# PSPS_AVNC_SRD_central-2020-09-19.net
KiCad netlist of a schematic drawn in EAGLE
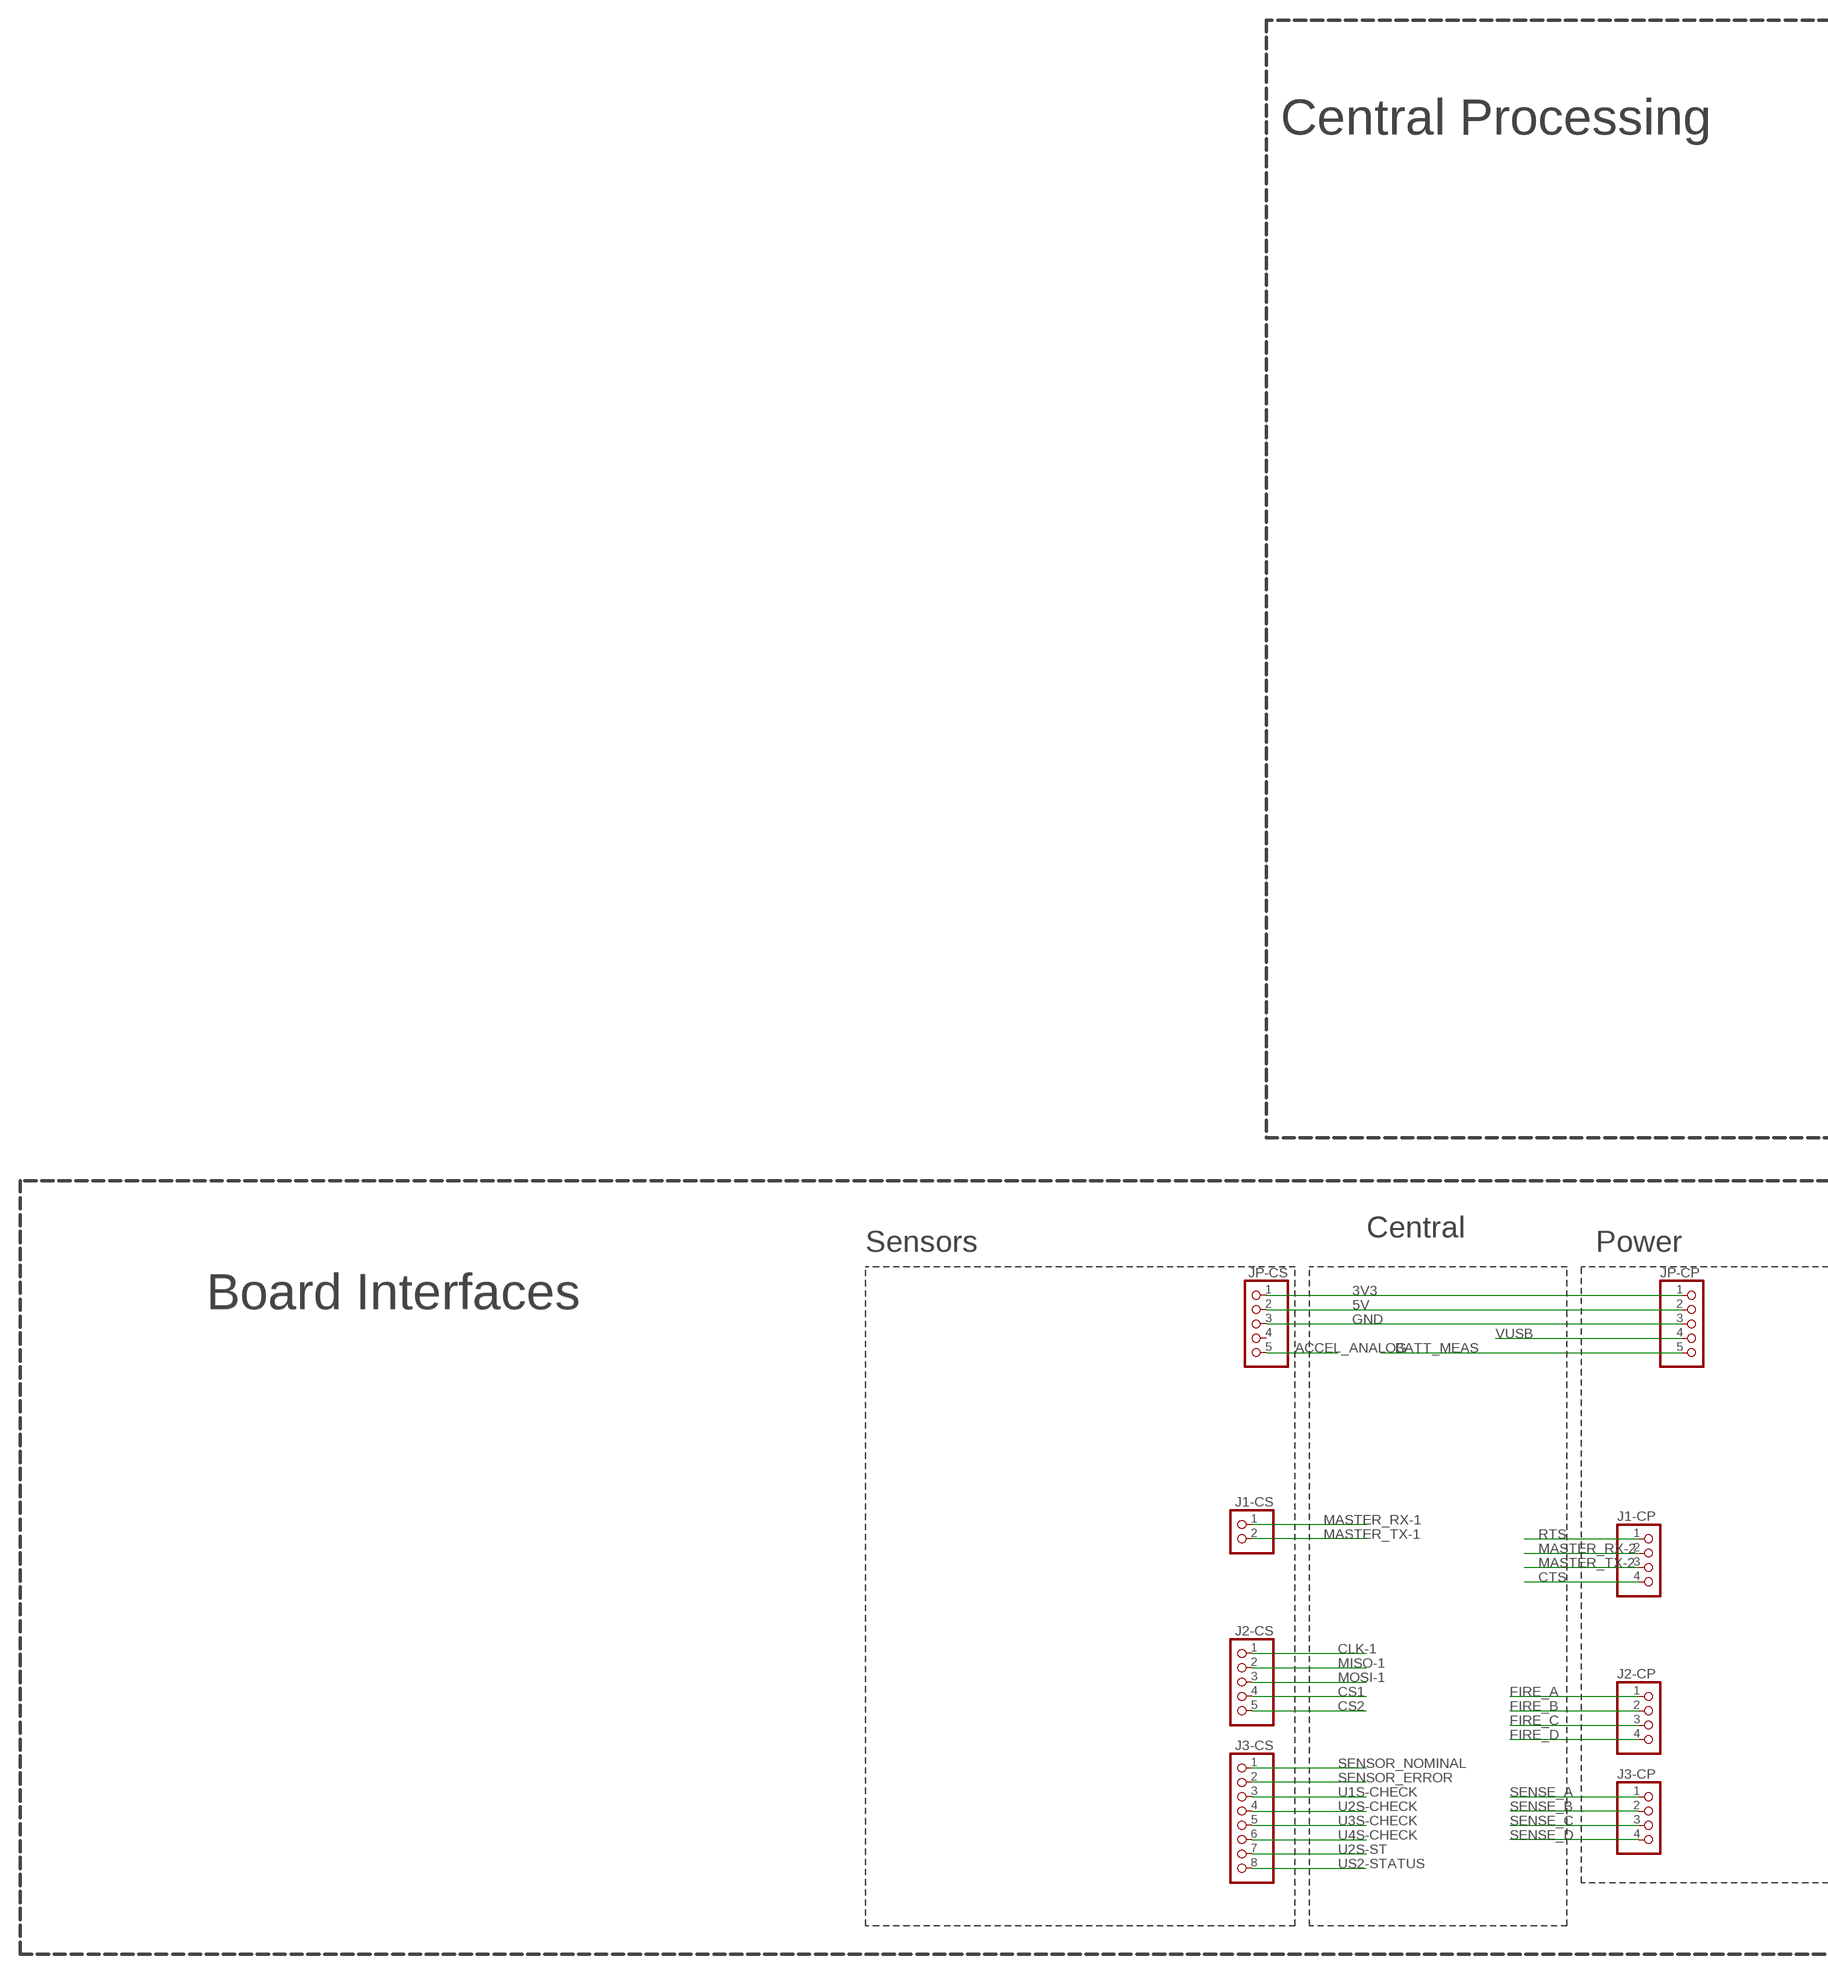
[diagram p0: schematic, sheet 1, part 1 of 2]
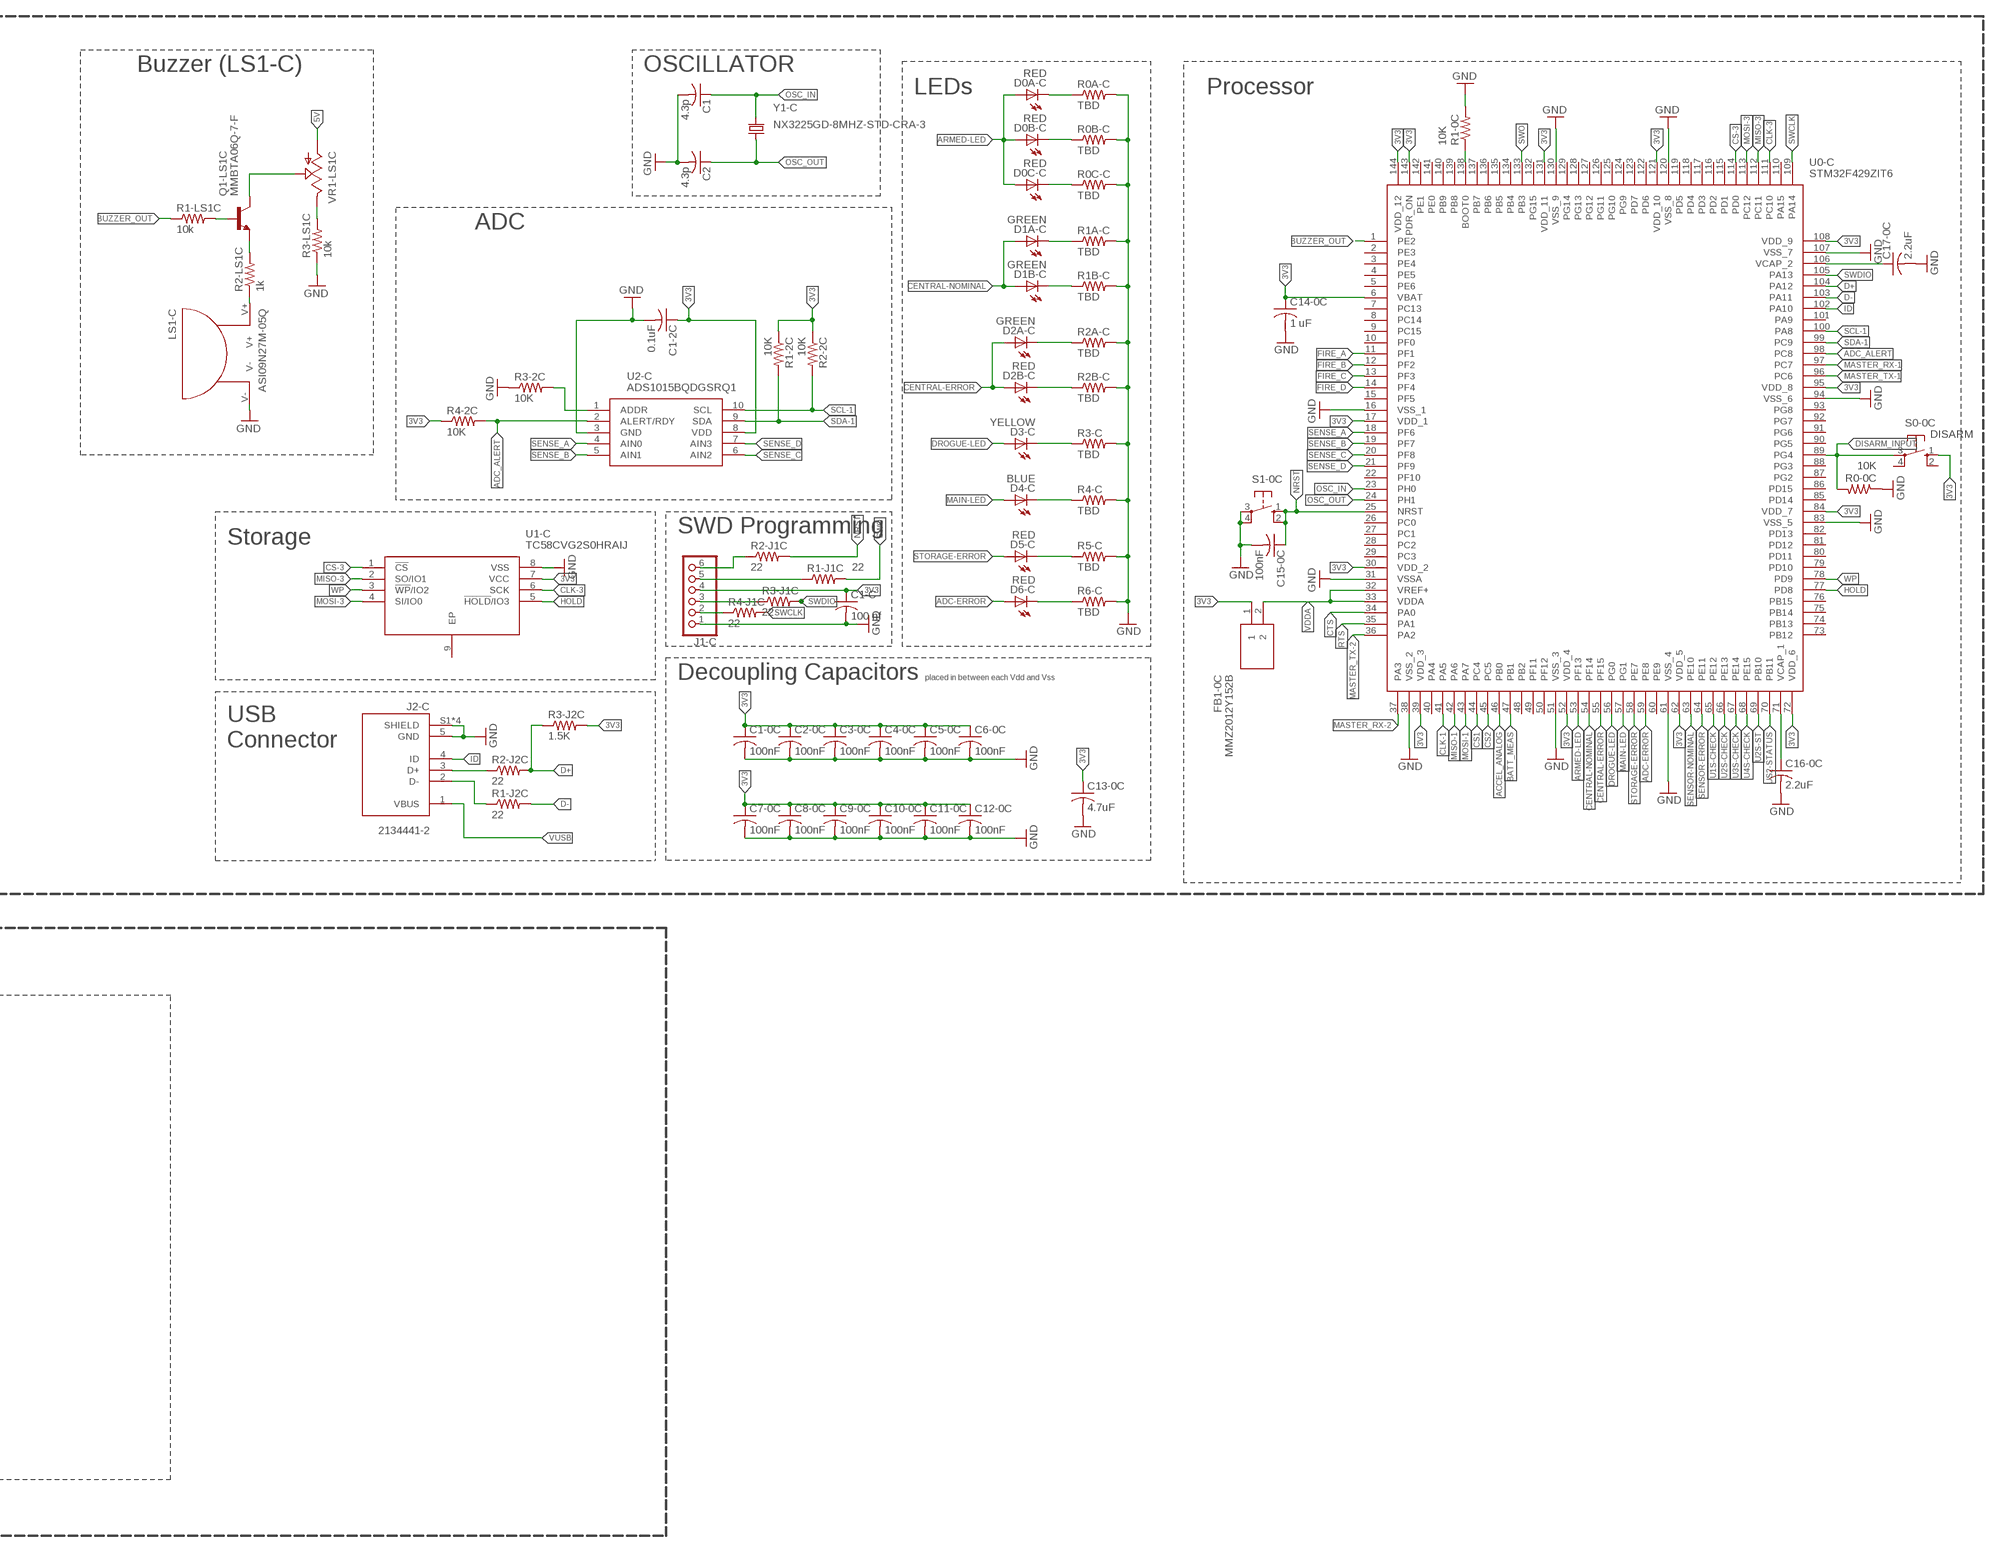
[diagram p1: schematic, sheet 1, part 2 of 2]

(export (version "E")
  (design (tool "Eeschema 10.0.6"))
  (components
    (comp (ref "C1")
      (value "4.3p")
      (footprint "eagle-import:C0805")
      (libsource (lib "eagle-import") (part "C-USC0805"))
    )
    (comp (ref "C1-0C")
      (value "100nF")
      (footprint "eagle-import:C0805")
      (libsource (lib "eagle-import") (part "C-USC0805"))
    )
    (comp (ref "C1-2C")
      (value "0.1uF")
      (footprint "eagle-import:C0805")
      (libsource (lib "eagle-import") (part "C-USC0805"))
    )
    (comp (ref "C1-C")
      (value "100 nf")
      (footprint "eagle-import:C0805")
      (libsource (lib "eagle-import") (part "C-USC0805"))
    )
    (comp (ref "C2")
      (value "4.3p")
      (footprint "eagle-import:C0805")
      (libsource (lib "eagle-import") (part "C-USC0805"))
    )
    (comp (ref "C2-0C")
      (value "100nF")
      (footprint "eagle-import:C0805")
      (libsource (lib "eagle-import") (part "C-USC0805"))
    )
    (comp (ref "C3-0C")
      (value "100nF")
      (footprint "eagle-import:C0805")
      (libsource (lib "eagle-import") (part "C-USC0805"))
    )
    (comp (ref "C4-0C")
      (value "100nF")
      (footprint "eagle-import:C0805")
      (libsource (lib "eagle-import") (part "C-USC0805"))
    )
    (comp (ref "C5-0C")
      (value "100nF")
      (footprint "eagle-import:C0805")
      (libsource (lib "eagle-import") (part "C-USC0805"))
    )
    (comp (ref "C6-0C")
      (value "100nF")
      (footprint "eagle-import:C0805")
      (libsource (lib "eagle-import") (part "C-USC0805"))
    )
    (comp (ref "C7-0C")
      (value "100nF")
      (footprint "eagle-import:C0805")
      (libsource (lib "eagle-import") (part "C-USC0805"))
    )
    (comp (ref "C8-0C")
      (value "100nF")
      (footprint "eagle-import:C0805")
      (libsource (lib "eagle-import") (part "C-USC0805"))
    )
    (comp (ref "C9-0C")
      (value "100nF")
      (footprint "eagle-import:C0805")
      (libsource (lib "eagle-import") (part "C-USC0805"))
    )
    (comp (ref "C10-0C")
      (value "100nF")
      (footprint "eagle-import:C0805")
      (libsource (lib "eagle-import") (part "C-USC0805"))
    )
    (comp (ref "C11-0C")
      (value "100nF")
      (footprint "eagle-import:C0805")
      (libsource (lib "eagle-import") (part "C-USC0805"))
    )
    (comp (ref "C12-0C")
      (value "100nF")
      (footprint "eagle-import:C0805")
      (libsource (lib "eagle-import") (part "C-USC0805"))
    )
    (comp (ref "C13-0C")
      (value "4.7uF")
      (footprint "eagle-import:C0805")
      (libsource (lib "eagle-import") (part "C-USC0805"))
    )
    (comp (ref "C14-0C")
      (value "1 uF")
      (footprint "eagle-import:C0805")
      (libsource (lib "eagle-import") (part "C-USC0805"))
    )
    (comp (ref "C15-0C")
      (value "100nF")
      (footprint "eagle-import:C0805")
      (libsource (lib "eagle-import") (part "C-USC0805"))
    )
    (comp (ref "C16-0C")
      (value "2.2uF")
      (footprint "eagle-import:C0805")
      (libsource (lib "eagle-import") (part "C-USC0805"))
    )
    (comp (ref "C17-0C")
      (value "2.2uF")
      (footprint "eagle-import:C0805")
      (libsource (lib "eagle-import") (part "C-USC0805"))
    )
    (comp (ref "D0A-C")
      (value "RED")
      (footprint "eagle-import:CHIPLED_0805")
      (libsource (lib "eagle-import") (part "LEDCHIPLED_0805"))
    )
    (comp (ref "D0B-C")
      (value "RED")
      (footprint "eagle-import:CHIPLED_0805")
      (libsource (lib "eagle-import") (part "LEDCHIPLED_0805"))
    )
    (comp (ref "D0C-C")
      (value "RED")
      (footprint "eagle-import:CHIPLED_0805")
      (libsource (lib "eagle-import") (part "LEDCHIPLED_0805"))
    )
    (comp (ref "D1A-C")
      (value "GREEN")
      (footprint "eagle-import:CHIPLED_0805")
      (libsource (lib "eagle-import") (part "LEDCHIPLED_0805"))
    )
    (comp (ref "D1B-C")
      (value "GREEN")
      (footprint "eagle-import:CHIPLED_0805")
      (libsource (lib "eagle-import") (part "LEDCHIPLED_0805"))
    )
    (comp (ref "D2A-C")
      (value "GREEN")
      (footprint "eagle-import:CHIPLED_0805")
      (libsource (lib "eagle-import") (part "LEDCHIPLED_0805"))
    )
    (comp (ref "D2B-C")
      (value "RED")
      (footprint "eagle-import:CHIPLED_0805")
      (libsource (lib "eagle-import") (part "LEDCHIPLED_0805"))
    )
    (comp (ref "D3-C")
      (value "YELLOW")
      (footprint "eagle-import:CHIPLED_0805")
      (libsource (lib "eagle-import") (part "LEDCHIPLED_0805"))
    )
    (comp (ref "D4-C")
      (value "BLUE")
      (footprint "eagle-import:CHIPLED_0805")
      (libsource (lib "eagle-import") (part "LEDCHIPLED_0805"))
    )
    (comp (ref "D5-C")
      (value "RED")
      (footprint "eagle-import:CHIPLED_0805")
      (libsource (lib "eagle-import") (part "LEDCHIPLED_0805"))
    )
    (comp (ref "D6-C")
      (value "RED")
      (footprint "eagle-import:CHIPLED_0805")
      (libsource (lib "eagle-import") (part "LEDCHIPLED_0805"))
    )
    (comp (ref "FB1-0C")
      (value "MMZ2012Y152B")
      (footprint "eagle-import:BEADC2012X105N")
      (fields (field (name "MOUSER_PART_NUMBER") "810-MMZ2012Y152B"))
      (libsource (lib "eagle-import") (part "MMZ2012Y152B"))
    )
    (comp (ref "J1-C")
      (value "PINHD-1X6")
      (footprint "eagle-import:1X06")
      (libsource (lib "eagle-import") (part "PINHD-1X6"))
    )
    (comp (ref "J1-CP")
      (value "PINHD-1X4")
      (footprint "eagle-import:1X04")
      (libsource (lib "eagle-import") (part "PINHD-1X4"))
    )
    (comp (ref "J1-CS")
      (value "PINHD-1X2")
      (footprint "eagle-import:1X02")
      (libsource (lib "eagle-import") (part "PINHD-1X2"))
    )
    (comp (ref "J2-C")
      (value "2134441-2")
      (footprint "eagle-import:TE_2134441-2")
      (fields (field (name "DIGI-KEY_PART_NUMBER") "A118104CT-ND") (field (name "MF") "TE Connectivity"))
      (libsource (lib "eagle-import") (part "2134441-2"))
    )
    (comp (ref "J2-CP")
      (value "PINHD-1X4")
      (footprint "eagle-import:1X04")
      (libsource (lib "eagle-import") (part "PINHD-1X4"))
    )
    (comp (ref "J2-CS")
      (value "PINHD-1X5")
      (footprint "eagle-import:1X05")
      (libsource (lib "eagle-import") (part "PINHD-1X5"))
    )
    (comp (ref "J3-CP")
      (value "PINHD-1X4")
      (footprint "eagle-import:1X04")
      (libsource (lib "eagle-import") (part "PINHD-1X4"))
    )
    (comp (ref "J3-CS")
      (value "PINHD-1X8")
      (footprint "eagle-import:1X08")
      (libsource (lib "eagle-import") (part "PINHD-1X8"))
    )
    (comp (ref "JP-CP")
      (value "PINHD-1X5")
      (footprint "eagle-import:1X05")
      (libsource (lib "eagle-import") (part "PINHD-1X5"))
    )
    (comp (ref "JP-CS")
      (value "PINHD-1X5")
      (footprint "eagle-import:1X05")
      (libsource (lib "eagle-import") (part "PINHD-1X5"))
    )
    (comp (ref "LS1-C")
      (value "ASI09N27M-05Q")
      (footprint "eagle-import:ASI09N27M-05Q")
      (libsource (lib "eagle-import") (part "ASI09N27M-05Q"))
    )
    (comp (ref "Q1-LS1C")
      (value "MMBTA06Q-7-F")
      (footprint "eagle-import:SOT23")
      (libsource (lib "eagle-import") (part "NPN_TRANSISTOR"))
    )
    (comp (ref "R0-0C")
      (value "10K")
      (footprint "eagle-import:R0805")
      (libsource (lib "eagle-import") (part "R-US_R0805"))
    )
    (comp (ref "R0A-C")
      (value "TBD")
      (footprint "eagle-import:M0805")
      (libsource (lib "eagle-import") (part "R-US_M0805"))
    )
    (comp (ref "R0B-C")
      (value "TBD")
      (footprint "eagle-import:M0805")
      (libsource (lib "eagle-import") (part "R-US_M0805"))
    )
    (comp (ref "R0C-C")
      (value "TBD")
      (footprint "eagle-import:M0805")
      (libsource (lib "eagle-import") (part "R-US_M0805"))
    )
    (comp (ref "R1-0C")
      (value "10K")
      (footprint "eagle-import:R0805")
      (libsource (lib "eagle-import") (part "R-US_R0805"))
    )
    (comp (ref "R1-2C")
      (value "10K")
      (footprint "eagle-import:R0805")
      (libsource (lib "eagle-import") (part "R-US_R0805"))
    )
    (comp (ref "R1-J1C")
      (value "22")
      (footprint "eagle-import:M0805")
      (libsource (lib "eagle-import") (part "R-US_M0805"))
    )
    (comp (ref "R1-J2C")
      (value "22")
      (footprint "eagle-import:M0805")
      (libsource (lib "eagle-import") (part "R-US_M0805"))
    )
    (comp (ref "R1-LS1C")
      (value "10k")
      (footprint "eagle-import:R0805")
      (libsource (lib "eagle-import") (part "resistor_348_R-US_R0805"))
    )
    (comp (ref "R1A-C")
      (value "TBD")
      (footprint "eagle-import:M0805")
      (libsource (lib "eagle-import") (part "R-US_M0805"))
    )
    (comp (ref "R1B-C")
      (value "TBD")
      (footprint "eagle-import:M0805")
      (libsource (lib "eagle-import") (part "R-US_M0805"))
    )
    (comp (ref "R2-2C")
      (value "10K")
      (footprint "eagle-import:R0805")
      (libsource (lib "eagle-import") (part "R-US_R0805"))
    )
    (comp (ref "R2-J1C")
      (value "22")
      (footprint "eagle-import:M0805")
      (libsource (lib "eagle-import") (part "R-US_M0805"))
    )
    (comp (ref "R2-J2C")
      (value "22")
      (footprint "eagle-import:M0805")
      (libsource (lib "eagle-import") (part "R-US_M0805"))
    )
    (comp (ref "R2-LS1C")
      (value "1k")
      (footprint "eagle-import:R0805")
      (libsource (lib "eagle-import") (part "resistor_348_R-US_R0805"))
    )
    (comp (ref "R2A-C")
      (value "TBD")
      (footprint "eagle-import:M0805")
      (libsource (lib "eagle-import") (part "R-US_M0805"))
    )
    (comp (ref "R2B-C")
      (value "TBD")
      (footprint "eagle-import:M0805")
      (libsource (lib "eagle-import") (part "R-US_M0805"))
    )
    (comp (ref "R3-2C")
      (value "10K")
      (footprint "eagle-import:R0805")
      (libsource (lib "eagle-import") (part "R-US_R0805"))
    )
    (comp (ref "R3-C")
      (value "TBD")
      (footprint "eagle-import:M0805")
      (libsource (lib "eagle-import") (part "R-US_M0805"))
    )
    (comp (ref "R3-J1C")
      (value "22")
      (footprint "eagle-import:M0805")
      (libsource (lib "eagle-import") (part "R-US_M0805"))
    )
    (comp (ref "R3-J2C")
      (value "1.5K")
      (footprint "eagle-import:M0805")
      (libsource (lib "eagle-import") (part "R-US_M0805"))
    )
    (comp (ref "R3-LS1C")
      (value "10k")
      (footprint "eagle-import:R0805")
      (libsource (lib "eagle-import") (part "resistor_348_R-US_R0805"))
    )
    (comp (ref "R4-2C")
      (value "10K")
      (footprint "eagle-import:R0805")
      (libsource (lib "eagle-import") (part "R-US_R0805"))
    )
    (comp (ref "R4-C")
      (value "TBD")
      (footprint "eagle-import:M0805")
      (libsource (lib "eagle-import") (part "R-US_M0805"))
    )
    (comp (ref "R4-J1C")
      (value "22")
      (footprint "eagle-import:M0805")
      (libsource (lib "eagle-import") (part "R-US_M0805"))
    )
    (comp (ref "R5-C")
      (value "TBD")
      (footprint "eagle-import:M0805")
      (libsource (lib "eagle-import") (part "R-US_M0805"))
    )
    (comp (ref "R6-C")
      (value "TBD")
      (footprint "eagle-import:M0805")
      (libsource (lib "eagle-import") (part "R-US_M0805"))
    )
    (comp (ref "S0-0C")
      (value "DISARM")
      (footprint "eagle-import:B3F-10XX")
      (fields (field (name "MPN") "B3F-1000"))
      (libsource (lib "eagle-import") (part "10-XX"))
    )
    (comp (ref "S1-0C")
      (value "10-XX")
      (footprint "eagle-import:B3F-10XX")
      (fields (field (name "MPN") "B3F-1000"))
      (libsource (lib "eagle-import") (part "10-XX"))
    )
    (comp (ref "U0-C")
      (value "STM32F429ZIT6")
      (footprint "eagle-import:QFP50P2200X2200X160-144N")
      (fields (field (name "MOUSER_PART_NUMBER") "511-STM32F429ZIT6"))
      (libsource (lib "eagle-import") (part "STM32F429ZIT6"))
    )
    (comp (ref "U1-C")
      (value "TC58CVG2S0HRAIJ")
      (footprint "eagle-import:SON127P800X600X80-9N")
      (fields (field (name "MOUSER_PART_NUMBER") "757-TC58CVG2S0HRAIJ"))
      (libsource (lib "eagle-import") (part "TC58CVG2S0HRAIJ"))
    )
    (comp (ref "U2-C")
      (value "ADS1015BQDGSRQ1")
      (footprint "eagle-import:SOP50P490X110-10N")
      (fields (field (name "MOUSER_PART_NUMBER") "595-ADS1015BQDGSRQ1"))
      (libsource (lib "eagle-import") (part "ADS1015BQDGSRQ1"))
    )
    (comp (ref "VR1-LS1C")
      (value "TRIM_US-LI10")
      (footprint "eagle-import:LI10")
      (libsource (lib "eagle-import") (part "TRIM_US-LI10"))
    )
    (comp (ref "Y1-C")
      (value "NX3225GD-8MHZ-STD-CRA-3")
      (footprint "eagle-import:3.2X2.5_KX-7")
      (libsource (lib "eagle-import") (part "KX-7"))
    )
  )
  (nets
    (net (code "1") (name "/SENSOR_ERROR") (class "Default")
      (node (ref "J3-CS") (pin "2") (pinfunction "2_2") (pintype "passive"))
    )
    (net (code "2") (name "/SENSOR_NOMINAL") (class "Default")
      (node (ref "J3-CS") (pin "1") (pinfunction "1_1") (pintype "passive"))
    )
    (net (code "3") (name "3V3") (class "Default")
      (node (ref "C1-0C") (pin "1") (pinfunction "1_1") (pintype "passive"))
      (node (ref "C1-2C") (pin "1") (pinfunction "1_1") (pintype "passive"))
      (node (ref "C1-C") (pin "1") (pinfunction "1_1") (pintype "passive"))
      (node (ref "C10-0C") (pin "1") (pinfunction "1_1") (pintype "passive"))
      (node (ref "C11-0C") (pin "1") (pinfunction "1_1") (pintype "passive"))
      (node (ref "C12-0C") (pin "1") (pinfunction "1_1") (pintype "passive"))
      (node (ref "C13-0C") (pin "1") (pinfunction "1_1") (pintype "passive"))
      (node (ref "C14-0C") (pin "1") (pinfunction "1_1") (pintype "passive"))
      (node (ref "C2-0C") (pin "1") (pinfunction "1_1") (pintype "passive"))
      (node (ref "C3-0C") (pin "1") (pinfunction "1_1") (pintype "passive"))
      (node (ref "C4-0C") (pin "1") (pinfunction "1_1") (pintype "passive"))
      (node (ref "C5-0C") (pin "1") (pinfunction "1_1") (pintype "passive"))
      (node (ref "C6-0C") (pin "1") (pinfunction "1_1") (pintype "passive"))
      (node (ref "C7-0C") (pin "1") (pinfunction "1_1") (pintype "passive"))
      (node (ref "C8-0C") (pin "1") (pinfunction "1_1") (pintype "passive"))
      (node (ref "C9-0C") (pin "1") (pinfunction "1_1") (pintype "passive"))
      (node (ref "FB1-0C") (pin "1") (pinfunction "1_1") (pintype "bidirectional"))
      (node (ref "J1-C") (pin "4") (pinfunction "4_4") (pintype "passive"))
      (node (ref "JP-CP") (pin "1") (pinfunction "1_1") (pintype "passive"))
      (node (ref "JP-CS") (pin "1") (pinfunction "1_1") (pintype "passive"))
      (node (ref "R1-2C") (pin "1") (pinfunction "1_1") (pintype "passive"))
      (node (ref "R2-2C") (pin "1") (pinfunction "1_1") (pintype "passive"))
      (node (ref "R3-J2C") (pin "2") (pinfunction "2_2") (pintype "passive"))
      (node (ref "R4-2C") (pin "1") (pinfunction "1_1") (pintype "passive"))
      (node (ref "S0-0C") (pin "1") (pinfunction "S_1") (pintype "passive"))
      (node (ref "U0-C") (pin "108") (pinfunction "VDD_9_108") (pintype "power_in"))
      (node (ref "U0-C") (pin "121") (pinfunction "VDD_10_121") (pintype "power_in"))
      (node (ref "U0-C") (pin "131") (pinfunction "VDD_11_131") (pintype "power_in"))
      (node (ref "U0-C") (pin "143") (pinfunction "PDR_ON_143") (pintype "bidirectional"))
      (node (ref "U0-C") (pin "144") (pinfunction "VDD_12_144") (pintype "power_in"))
      (node (ref "U0-C") (pin "17") (pinfunction "VDD_1_17") (pintype "power_in"))
      (node (ref "U0-C") (pin "30") (pinfunction "VDD_2_30") (pintype "power_in"))
      (node (ref "U0-C") (pin "39") (pinfunction "VDD_3_39") (pintype "power_in"))
      (node (ref "U0-C") (pin "52") (pinfunction "VDD_4_52") (pintype "power_in"))
      (node (ref "U0-C") (pin "6") (pinfunction "VBAT_6") (pintype "bidirectional"))
      (node (ref "U0-C") (pin "62") (pinfunction "VDD_5_62") (pintype "power_in"))
      (node (ref "U0-C") (pin "72") (pinfunction "VDD_6_72") (pintype "power_in"))
      (node (ref "U0-C") (pin "84") (pinfunction "VDD_7_84") (pintype "power_in"))
      (node (ref "U0-C") (pin "95") (pinfunction "VDD_8_95") (pintype "power_in"))
      (node (ref "U1-C") (pin "7") (pinfunction "VCC_7") (pintype "bidirectional"))
      (node (ref "U2-C") (pin "8") (pinfunction "VDD_8") (pintype "bidirectional"))
    )
    (net (code "4") (name "5V") (class "Default")
      (node (ref "JP-CP") (pin "2") (pinfunction "2_2") (pintype "passive"))
      (node (ref "JP-CS") (pin "2") (pinfunction "2_2") (pintype "passive"))
      (node (ref "VR1-LS1C") (pin "A") (pinfunction "A_A") (pintype "passive"))
    )
    (net (code "5") (name "ACCEL_ANALOG") (class "Default")
      (node (ref "JP-CS") (pin "5") (pinfunction "5_5") (pintype "passive"))
      (node (ref "U0-C") (pin "46") (pinfunction "PB0_46") (pintype "bidirectional"))
    )
    (net (code "6") (name "ADC-ERROR") (class "Default")
      (node (ref "D6-C") (pin "A") (pinfunction "A_A") (pintype "passive"))
      (node (ref "U0-C") (pin "59") (pinfunction "PE8_59") (pintype "bidirectional"))
    )
    (net (code "7") (name "ADC_ALERT") (class "Default")
      (node (ref "R4-2C") (pin "2") (pinfunction "2_2") (pintype "passive"))
      (node (ref "U0-C") (pin "98") (pinfunction "PC8_98") (pintype "bidirectional"))
      (node (ref "U2-C") (pin "2") (pinfunction "ALERT/RDY_2") (pintype "bidirectional"))
    )
    (net (code "8") (name "ARMED-LED") (class "Default")
      (node (ref "D0A-C") (pin "A") (pinfunction "A_A") (pintype "passive"))
      (node (ref "D0B-C") (pin "A") (pinfunction "A_A") (pintype "passive"))
      (node (ref "D0C-C") (pin "A") (pinfunction "A_A") (pintype "passive"))
      (node (ref "U0-C") (pin "53") (pinfunction "PF13_53") (pintype "bidirectional"))
    )
    (net (code "9") (name "BATT_MEAS") (class "Default")
      (node (ref "JP-CP") (pin "5") (pinfunction "5_5") (pintype "passive"))
      (node (ref "U0-C") (pin "47") (pinfunction "PB1_47") (pintype "bidirectional"))
    )
    (net (code "10") (name "BUZZER_OUT") (class "Default")
      (node (ref "R1-LS1C") (pin "1") (pinfunction "1_1") (pintype "passive"))
      (node (ref "U0-C") (pin "1") (pinfunction "PE2_1") (pintype "bidirectional"))
    )
    (net (code "11") (name "CENTRAL-ERROR") (class "Default")
      (node (ref "D2A-C") (pin "A") (pinfunction "A_A") (pintype "passive"))
      (node (ref "D2B-C") (pin "A") (pinfunction "A_A") (pintype "passive"))
      (node (ref "U0-C") (pin "55") (pinfunction "PF15_55") (pintype "bidirectional"))
    )
    (net (code "12") (name "CENTRAL-NOMINAL") (class "Default")
      (node (ref "D1A-C") (pin "A") (pinfunction "A_A") (pintype "passive"))
      (node (ref "D1B-C") (pin "A") (pinfunction "A_A") (pintype "passive"))
      (node (ref "U0-C") (pin "54") (pinfunction "PF14_54") (pintype "bidirectional"))
    )
    (net (code "13") (name "CLK-1") (class "Default")
      (node (ref "J2-CS") (pin "1") (pinfunction "1_1") (pintype "passive"))
      (node (ref "U0-C") (pin "41") (pinfunction "PA5_41") (pintype "bidirectional"))
    )
    (net (code "14") (name "CLK-3") (class "Default")
      (node (ref "U0-C") (pin "111") (pinfunction "PC10_111") (pintype "bidirectional"))
      (node (ref "U1-C") (pin "6") (pinfunction "SCK_6") (pintype "bidirectional"))
    )
    (net (code "15") (name "CS-3") (class "Default")
      (node (ref "U0-C") (pin "114") (pinfunction "PD0_114") (pintype "bidirectional"))
      (node (ref "U1-C") (pin "1") (pinfunction "~{CS}_1") (pintype "bidirectional"))
    )
    (net (code "16") (name "CS1") (class "Default")
      (node (ref "J2-CS") (pin "4") (pinfunction "4_4") (pintype "passive"))
      (node (ref "U0-C") (pin "44") (pinfunction "PC4_44") (pintype "bidirectional"))
    )
    (net (code "17") (name "CS2") (class "Default")
      (node (ref "J2-CS") (pin "5") (pinfunction "5_5") (pintype "passive"))
      (node (ref "U0-C") (pin "45") (pinfunction "PC5_45") (pintype "bidirectional"))
    )
    (net (code "18") (name "CTS") (class "Default")
      (node (ref "J1-CP") (pin "4") (pinfunction "4_4") (pintype "passive"))
      (node (ref "U0-C") (pin "34") (pinfunction "PA0_34") (pintype "bidirectional"))
    )
    (net (code "19") (name "D+") (class "Default")
      (node (ref "R2-J2C") (pin "2") (pinfunction "2_2") (pintype "passive"))
      (node (ref "R3-J2C") (pin "1") (pinfunction "1_1") (pintype "passive"))
      (node (ref "U0-C") (pin "104") (pinfunction "PA12_104") (pintype "bidirectional"))
    )
    (net (code "20") (name "D-") (class "Default")
      (node (ref "R1-J2C") (pin "2") (pinfunction "2_2") (pintype "passive"))
      (node (ref "U0-C") (pin "103") (pinfunction "PA11_103") (pintype "bidirectional"))
    )
    (net (code "21") (name "DISARM_INPUT") (class "Default")
      (node (ref "R0-0C") (pin "2") (pinfunction "2_2") (pintype "passive"))
      (node (ref "S0-0C") (pin "3") (pinfunction "P_3") (pintype "passive"))
      (node (ref "U0-C") (pin "89") (pinfunction "PG4_89") (pintype "bidirectional"))
    )
    (net (code "22") (name "DROGUE-LED") (class "Default")
      (node (ref "D3-C") (pin "A") (pinfunction "A_A") (pintype "passive"))
      (node (ref "U0-C") (pin "56") (pinfunction "PG0_56") (pintype "bidirectional"))
    )
    (net (code "23") (name "FIRE_A") (class "Default")
      (node (ref "J2-CP") (pin "1") (pinfunction "1_1") (pintype "passive"))
      (node (ref "U0-C") (pin "11") (pinfunction "PF1_11") (pintype "bidirectional"))
    )
    (net (code "24") (name "FIRE_B") (class "Default")
      (node (ref "J2-CP") (pin "2") (pinfunction "2_2") (pintype "passive"))
      (node (ref "U0-C") (pin "12") (pinfunction "PF2_12") (pintype "bidirectional"))
    )
    (net (code "25") (name "FIRE_C") (class "Default")
      (node (ref "J2-CP") (pin "3") (pinfunction "3_3") (pintype "passive"))
      (node (ref "U0-C") (pin "13") (pinfunction "PF3_13") (pintype "bidirectional"))
    )
    (net (code "26") (name "FIRE_D") (class "Default")
      (node (ref "J2-CP") (pin "4") (pinfunction "4_4") (pintype "passive"))
      (node (ref "U0-C") (pin "14") (pinfunction "PF4_14") (pintype "bidirectional"))
    )
    (net (code "27") (name "GND") (class "Default")
      (node (ref "C1") (pin "2") (pinfunction "2_2") (pintype "passive"))
      (node (ref "C1-0C") (pin "2") (pinfunction "2_2") (pintype "passive"))
      (node (ref "C1-2C") (pin "2") (pinfunction "2_2") (pintype "passive"))
      (node (ref "C1-C") (pin "2") (pinfunction "2_2") (pintype "passive"))
      (node (ref "C10-0C") (pin "2") (pinfunction "2_2") (pintype "passive"))
      (node (ref "C11-0C") (pin "2") (pinfunction "2_2") (pintype "passive"))
      (node (ref "C12-0C") (pin "2") (pinfunction "2_2") (pintype "passive"))
      (node (ref "C13-0C") (pin "2") (pinfunction "2_2") (pintype "passive"))
      (node (ref "C14-0C") (pin "2") (pinfunction "2_2") (pintype "passive"))
      (node (ref "C15-0C") (pin "2") (pinfunction "2_2") (pintype "passive"))
      (node (ref "C16-0C") (pin "2") (pinfunction "2_2") (pintype "passive"))
      (node (ref "C17-0C") (pin "2") (pinfunction "2_2") (pintype "passive"))
      (node (ref "C2") (pin "2") (pinfunction "2_2") (pintype "passive"))
      (node (ref "C2-0C") (pin "2") (pinfunction "2_2") (pintype "passive"))
      (node (ref "C3-0C") (pin "2") (pinfunction "2_2") (pintype "passive"))
      (node (ref "C4-0C") (pin "2") (pinfunction "2_2") (pintype "passive"))
      (node (ref "C5-0C") (pin "2") (pinfunction "2_2") (pintype "passive"))
      (node (ref "C6-0C") (pin "2") (pinfunction "2_2") (pintype "passive"))
      (node (ref "C7-0C") (pin "2") (pinfunction "2_2") (pintype "passive"))
      (node (ref "C8-0C") (pin "2") (pinfunction "2_2") (pintype "passive"))
      (node (ref "C9-0C") (pin "2") (pinfunction "2_2") (pintype "passive"))
      (node (ref "J1-C") (pin "1") (pinfunction "1_1") (pintype "passive"))
      (node (ref "J2-C") (pin "5") (pinfunction "GND_5") (pintype "power_in"))
      (node (ref "J2-C") (pin "S1") (pinfunction "SHIELD_S1") (pintype "power_in"))
      (node (ref "J2-C") (pin "S2") (pinfunction "SHIELD_S2") (pintype "power_in"))
      (node (ref "J2-C") (pin "S3") (pinfunction "SHIELD_S3") (pintype "power_in"))
      (node (ref "J2-C") (pin "S4") (pinfunction "SHIELD_S4") (pintype "power_in"))
      (node (ref "JP-CP") (pin "3") (pinfunction "3_3") (pintype "passive"))
      (node (ref "JP-CS") (pin "3") (pinfunction "3_3") (pintype "passive"))
      (node (ref "LS1-C") (pin "V-") (pinfunction "V-_V-") (pintype "bidirectional"))
      (node (ref "R0-0C") (pin "1") (pinfunction "1_1") (pintype "passive"))
      (node (ref "R0A-C") (pin "2") (pinfunction "2_2") (pintype "passive"))
      (node (ref "R0B-C") (pin "2") (pinfunction "2_2") (pintype "passive"))
      (node (ref "R0C-C") (pin "2") (pinfunction "2_2") (pintype "passive"))
      (node (ref "R1-0C") (pin "2") (pinfunction "2_2") (pintype "passive"))
      (node (ref "R1A-C") (pin "2") (pinfunction "2_2") (pintype "passive"))
      (node (ref "R1B-C") (pin "2") (pinfunction "2_2") (pintype "passive"))
      (node (ref "R2A-C") (pin "2") (pinfunction "2_2") (pintype "passive"))
      (node (ref "R2B-C") (pin "2") (pinfunction "2_2") (pintype "passive"))
      (node (ref "R3-2C") (pin "1") (pinfunction "1_1") (pintype "passive"))
      (node (ref "R3-C") (pin "2") (pinfunction "2_2") (pintype "passive"))
      (node (ref "R3-LS1C") (pin "1") (pinfunction "1_1") (pintype "passive"))
      (node (ref "R4-C") (pin "2") (pinfunction "2_2") (pintype "passive"))
      (node (ref "R5-C") (pin "2") (pinfunction "2_2") (pintype "passive"))
      (node (ref "R6-C") (pin "2") (pinfunction "2_2") (pintype "passive"))
      (node (ref "S1-0C") (pin "3") (pinfunction "P_3") (pintype "passive"))
      (node (ref "S1-0C") (pin "4") (pinfunction "P1_4") (pintype "passive"))
      (node (ref "U0-C") (pin "107") (pinfunction "VSS_7_107") (pintype "power_in"))
      (node (ref "U0-C") (pin "120") (pinfunction "VSS_8_120") (pintype "power_in"))
      (node (ref "U0-C") (pin "130") (pinfunction "VSS_9_130") (pintype "power_in"))
      (node (ref "U0-C") (pin "16") (pinfunction "VSS_1_16") (pintype "power_in"))
      (node (ref "U0-C") (pin "31") (pinfunction "VSSA_31") (pintype "power_in"))
      (node (ref "U0-C") (pin "38") (pinfunction "VSS_2_38") (pintype "power_in"))
      (node (ref "U0-C") (pin "51") (pinfunction "VSS_3_51") (pintype "power_in"))
      (node (ref "U0-C") (pin "61") (pinfunction "VSS_4_61") (pintype "power_in"))
      (node (ref "U0-C") (pin "83") (pinfunction "VSS_5_83") (pintype "power_in"))
      (node (ref "U0-C") (pin "94") (pinfunction "VSS_6_94") (pintype "power_in"))
      (node (ref "U1-C") (pin "8") (pinfunction "VSS_8") (pintype "bidirectional"))
      (node (ref "U2-C") (pin "3") (pinfunction "GND_3") (pintype "bidirectional"))
    )
    (net (code "28") (name "HOLD") (class "Default")
      (node (ref "U0-C") (pin "77") (pinfunction "PD8_77") (pintype "bidirectional"))
      (node (ref "U1-C") (pin "5") (pinfunction "~{HOLD}/IO3_5") (pintype "bidirectional"))
    )
    (net (code "29") (name "ID") (class "Default")
      (node (ref "J2-C") (pin "4") (pinfunction "ID_4") (pintype "bidirectional"))
      (node (ref "U0-C") (pin "102") (pinfunction "PA10_102") (pintype "bidirectional"))
    )
    (net (code "30") (name "MAIN-LED") (class "Default")
      (node (ref "D4-C") (pin "A") (pinfunction "A_A") (pintype "passive"))
      (node (ref "U0-C") (pin "57") (pinfunction "PG1_57") (pintype "bidirectional"))
    )
    (net (code "31") (name "MASTER_RX-1") (class "Default")
      (node (ref "J1-CS") (pin "1") (pinfunction "1_1") (pintype "passive"))
      (node (ref "U0-C") (pin "97") (pinfunction "PC7_97") (pintype "bidirectional"))
    )
    (net (code "32") (name "MASTER_RX-2") (class "Default")
      (node (ref "J1-CP") (pin "2") (pinfunction "2_2") (pintype "passive"))
      (node (ref "U0-C") (pin "37") (pinfunction "PA3_37") (pintype "bidirectional"))
    )
    (net (code "33") (name "MASTER_TX-1") (class "Default")
      (node (ref "J1-CS") (pin "2") (pinfunction "2_2") (pintype "passive"))
      (node (ref "U0-C") (pin "96") (pinfunction "PC6_96") (pintype "bidirectional"))
    )
    (net (code "34") (name "MASTER_TX-2") (class "Default")
      (node (ref "J1-CP") (pin "3") (pinfunction "3_3") (pintype "passive"))
      (node (ref "U0-C") (pin "36") (pinfunction "PA2_36") (pintype "bidirectional"))
    )
    (net (code "35") (name "MISO-1") (class "Default")
      (node (ref "J2-CS") (pin "2") (pinfunction "2_2") (pintype "passive"))
      (node (ref "U0-C") (pin "42") (pinfunction "PA6_42") (pintype "bidirectional"))
    )
    (net (code "36") (name "MISO-3") (class "Default")
      (node (ref "U0-C") (pin "112") (pinfunction "PC11_112") (pintype "bidirectional"))
      (node (ref "U1-C") (pin "2") (pinfunction "SO/IO1_2") (pintype "bidirectional"))
    )
    (net (code "37") (name "MOSI-1") (class "Default")
      (node (ref "J2-CS") (pin "3") (pinfunction "3_3") (pintype "passive"))
      (node (ref "U0-C") (pin "43") (pinfunction "PA7_43") (pintype "bidirectional"))
    )
    (net (code "38") (name "MOSI-3") (class "Default")
      (node (ref "U0-C") (pin "113") (pinfunction "PC12_113") (pintype "bidirectional"))
      (node (ref "U1-C") (pin "4") (pinfunction "SI/IO0_4") (pintype "bidirectional"))
    )
    (net (code "39") (name "NRST") (class "Default")
      (node (ref "C15-0C") (pin "1") (pinfunction "1_1") (pintype "passive"))
      (node (ref "R2-J1C") (pin "2") (pinfunction "2_2") (pintype "passive"))
      (node (ref "S1-0C") (pin "1") (pinfunction "S_1") (pintype "passive"))
      (node (ref "S1-0C") (pin "2") (pinfunction "S1_2") (pintype "passive"))
      (node (ref "U0-C") (pin "25") (pinfunction "NRST_25") (pintype "input"))
    )
    (net (code "40") (name "Net-(D0A-C-PadC)") (class "Default")
      (node (ref "D0A-C") (pin "C") (pinfunction "C_C") (pintype "passive"))
      (node (ref "R0A-C") (pin "1") (pinfunction "1_1") (pintype "passive"))
    )
    (net (code "41") (name "Net-(D0B-C-PadC)") (class "Default")
      (node (ref "D0B-C") (pin "C") (pinfunction "C_C") (pintype "passive"))
      (node (ref "R0B-C") (pin "1") (pinfunction "1_1") (pintype "passive"))
    )
    (net (code "42") (name "Net-(D0C-C-PadC)") (class "Default")
      (node (ref "D0C-C") (pin "C") (pinfunction "C_C") (pintype "passive"))
      (node (ref "R0C-C") (pin "1") (pinfunction "1_1") (pintype "passive"))
    )
    (net (code "43") (name "Net-(D1A-C-PadC)") (class "Default")
      (node (ref "D1A-C") (pin "C") (pinfunction "C_C") (pintype "passive"))
      (node (ref "R1A-C") (pin "1") (pinfunction "1_1") (pintype "passive"))
    )
    (net (code "44") (name "Net-(D1B-C-PadC)") (class "Default")
      (node (ref "D1B-C") (pin "C") (pinfunction "C_C") (pintype "passive"))
      (node (ref "R1B-C") (pin "1") (pinfunction "1_1") (pintype "passive"))
    )
    (net (code "45") (name "Net-(D2A-C-PadC)") (class "Default")
      (node (ref "D2A-C") (pin "C") (pinfunction "C_C") (pintype "passive"))
      (node (ref "R2A-C") (pin "1") (pinfunction "1_1") (pintype "passive"))
    )
    (net (code "46") (name "Net-(D2B-C-PadC)") (class "Default")
      (node (ref "D2B-C") (pin "C") (pinfunction "C_C") (pintype "passive"))
      (node (ref "R2B-C") (pin "1") (pinfunction "1_1") (pintype "passive"))
    )
    (net (code "47") (name "Net-(D3-C-PadC)") (class "Default")
      (node (ref "D3-C") (pin "C") (pinfunction "C_C") (pintype "passive"))
      (node (ref "R3-C") (pin "1") (pinfunction "1_1") (pintype "passive"))
    )
    (net (code "48") (name "Net-(D4-C-PadC)") (class "Default")
      (node (ref "D4-C") (pin "C") (pinfunction "C_C") (pintype "passive"))
      (node (ref "R4-C") (pin "1") (pinfunction "1_1") (pintype "passive"))
    )
    (net (code "49") (name "Net-(D5-C-PadC)") (class "Default")
      (node (ref "D5-C") (pin "C") (pinfunction "C_C") (pintype "passive"))
      (node (ref "R5-C") (pin "1") (pinfunction "1_1") (pintype "passive"))
    )
    (net (code "50") (name "Net-(D6-C-PadC)") (class "Default")
      (node (ref "D6-C") (pin "C") (pinfunction "C_C") (pintype "passive"))
      (node (ref "R6-C") (pin "1") (pinfunction "1_1") (pintype "passive"))
    )
    (net (code "51") (name "Net-(J1-C-Pad5)") (class "Default")
      (node (ref "J1-C") (pin "5") (pinfunction "5_5") (pintype "passive"))
      (node (ref "R1-J1C") (pin "1") (pinfunction "1_1") (pintype "passive"))
    )
    (net (code "52") (name "Net-(J1-C-Pad6)") (class "Default")
      (node (ref "J1-C") (pin "6") (pinfunction "6_6") (pintype "passive"))
      (node (ref "R2-J1C") (pin "1") (pinfunction "1_1") (pintype "passive"))
    )
    (net (code "53") (name "Net-(J2-C-D+)") (class "Default")
      (node (ref "J2-C") (pin "3") (pinfunction "D+_3") (pintype "bidirectional"))
      (node (ref "R2-J2C") (pin "1") (pinfunction "1_1") (pintype "passive"))
    )
    (net (code "54") (name "Net-(J2-C-D-)") (class "Default")
      (node (ref "J2-C") (pin "2") (pinfunction "D-_2") (pintype "bidirectional"))
      (node (ref "R1-J2C") (pin "1") (pinfunction "1_1") (pintype "passive"))
    )
    (net (code "55") (name "Net-(LS1-C-PadV+)") (class "Default")
      (node (ref "LS1-C") (pin "V+") (pinfunction "V+_V+") (pintype "bidirectional"))
      (node (ref "R2-LS1C") (pin "1") (pinfunction "1_1") (pintype "passive"))
    )
    (net (code "56") (name "Net-(Q1-LS1C-B)") (class "Default")
      (node (ref "Q1-LS1C") (pin "1") (pinfunction "B_1") (pintype "passive"))
      (node (ref "R1-LS1C") (pin "2") (pinfunction "2_2") (pintype "passive"))
    )
    (net (code "57") (name "Net-(Q1-LS1C-C)") (class "Default")
      (node (ref "Q1-LS1C") (pin "2") (pinfunction "C_2") (pintype "passive"))
      (node (ref "VR1-LS1C") (pin "S") (pinfunction "S_S") (pintype "passive"))
    )
    (net (code "58") (name "Net-(Q1-LS1C-E)") (class "Default")
      (node (ref "Q1-LS1C") (pin "3") (pinfunction "E_3") (pintype "passive"))
      (node (ref "R2-LS1C") (pin "2") (pinfunction "2_2") (pintype "passive"))
    )
    (net (code "59") (name "Net-(R3-LS1C-Pad2)") (class "Default")
      (node (ref "R3-LS1C") (pin "2") (pinfunction "2_2") (pintype "passive"))
      (node (ref "VR1-LS1C") (pin "E") (pinfunction "E_E") (pintype "passive"))
    )
    (net (code "60") (name "Net-(U0-C-BOOT0)") (class "Default")
      (node (ref "R1-0C") (pin "1") (pinfunction "1_1") (pintype "passive"))
      (node (ref "U0-C") (pin "138") (pinfunction "BOOT0_138") (pintype "bidirectional"))
    )
    (net (code "61") (name "Net-(U0-C-VCAP_1)") (class "Default")
      (node (ref "C16-0C") (pin "1") (pinfunction "1_1") (pintype "passive"))
      (node (ref "U0-C") (pin "71") (pinfunction "VCAP_1_71") (pintype "bidirectional"))
    )
    (net (code "62") (name "Net-(U0-C-VCAP_2)") (class "Default")
      (node (ref "C17-0C") (pin "1") (pinfunction "1_1") (pintype "passive"))
      (node (ref "U0-C") (pin "106") (pinfunction "VCAP_2_106") (pintype "bidirectional"))
    )
    (net (code "63") (name "Net-(U2-C-ADDR)") (class "Default")
      (node (ref "R3-2C") (pin "2") (pinfunction "2_2") (pintype "passive"))
      (node (ref "U2-C") (pin "1") (pinfunction "ADDR_1") (pintype "bidirectional"))
    )
    (net (code "64") (name "OSC_IN") (class "Default")
      (node (ref "C1") (pin "1") (pinfunction "1_1") (pintype "passive"))
      (node (ref "U0-C") (pin "23") (pinfunction "PH0_23") (pintype "bidirectional"))
      (node (ref "Y1-C") (pin "3") (pinfunction "2_3") (pintype "passive"))
    )
    (net (code "65") (name "OSC_OUT") (class "Default")
      (node (ref "C2") (pin "1") (pinfunction "1_1") (pintype "passive"))
      (node (ref "U0-C") (pin "24") (pinfunction "PH1_24") (pintype "bidirectional"))
      (node (ref "Y1-C") (pin "1") (pinfunction "1_1") (pintype "passive"))
    )
    (net (code "66") (name "RTS") (class "Default")
      (node (ref "J1-CP") (pin "1") (pinfunction "1_1") (pintype "passive"))
      (node (ref "U0-C") (pin "35") (pinfunction "PA1_35") (pintype "bidirectional"))
    )
    (net (code "67") (name "SCL-1") (class "Default")
      (node (ref "R2-2C") (pin "2") (pinfunction "2_2") (pintype "passive"))
      (node (ref "U0-C") (pin "100") (pinfunction "PA8_100") (pintype "bidirectional"))
      (node (ref "U2-C") (pin "10") (pinfunction "SCL_10") (pintype "bidirectional"))
    )
    (net (code "68") (name "SDA-1") (class "Default")
      (node (ref "R1-2C") (pin "2") (pinfunction "2_2") (pintype "passive"))
      (node (ref "U0-C") (pin "99") (pinfunction "PC9_99") (pintype "bidirectional"))
      (node (ref "U2-C") (pin "9") (pinfunction "SDA_9") (pintype "bidirectional"))
    )
    (net (code "69") (name "SENSE_A") (class "Default")
      (node (ref "J3-CP") (pin "1") (pinfunction "1_1") (pintype "passive"))
      (node (ref "U0-C") (pin "18") (pinfunction "PF6_18") (pintype "bidirectional"))
      (node (ref "U2-C") (pin "4") (pinfunction "AIN0_4") (pintype "bidirectional"))
    )
    (net (code "70") (name "SENSE_B") (class "Default")
      (node (ref "J3-CP") (pin "2") (pinfunction "2_2") (pintype "passive"))
      (node (ref "U0-C") (pin "19") (pinfunction "PF7_19") (pintype "bidirectional"))
      (node (ref "U2-C") (pin "5") (pinfunction "AIN1_5") (pintype "bidirectional"))
    )
    (net (code "71") (name "SENSE_C") (class "Default")
      (node (ref "J3-CP") (pin "3") (pinfunction "3_3") (pintype "passive"))
      (node (ref "U0-C") (pin "20") (pinfunction "PF8_20") (pintype "bidirectional"))
      (node (ref "U2-C") (pin "6") (pinfunction "AIN2_6") (pintype "bidirectional"))
    )
    (net (code "72") (name "SENSE_D") (class "Default")
      (node (ref "J3-CP") (pin "4") (pinfunction "4_4") (pintype "passive"))
      (node (ref "U0-C") (pin "21") (pinfunction "PF9_21") (pintype "bidirectional"))
      (node (ref "U2-C") (pin "7") (pinfunction "AIN3_7") (pintype "bidirectional"))
    )
    (net (code "73") (name "SENSOR-ERROR") (class "Default")
      (node (ref "U0-C") (pin "64") (pinfunction "PE11_64") (pintype "bidirectional"))
    )
    (net (code "74") (name "SENSOR-NOMINAL") (class "Default")
      (node (ref "U0-C") (pin "63") (pinfunction "PE10_63") (pintype "bidirectional"))
    )
    (net (code "75") (name "STORAGE-ERROR") (class "Default")
      (node (ref "D5-C") (pin "A") (pinfunction "A_A") (pintype "passive"))
      (node (ref "U0-C") (pin "58") (pinfunction "PE7_58") (pintype "bidirectional"))
    )
    (net (code "76") (name "SWCLK") (class "Default")
      (node (ref "J1-C") (pin "2") (pinfunction "2_2") (pintype "passive"))
      (node (ref "R4-J1C") (pin "1") (pinfunction "1_1") (pintype "passive"))
      (node (ref "R4-J1C") (pin "2") (pinfunction "2_2") (pintype "passive"))
      (node (ref "U0-C") (pin "109") (pinfunction "PA14_109") (pintype "bidirectional"))
    )
    (net (code "77") (name "SWDIO") (class "Default")
      (node (ref "J1-C") (pin "3") (pinfunction "3_3") (pintype "passive"))
      (node (ref "R3-J1C") (pin "1") (pinfunction "1_1") (pintype "passive"))
      (node (ref "R3-J1C") (pin "2") (pinfunction "2_2") (pintype "passive"))
      (node (ref "U0-C") (pin "105") (pinfunction "PA13_105") (pintype "bidirectional"))
    )
    (net (code "78") (name "SWO") (class "Default")
      (node (ref "R1-J1C") (pin "2") (pinfunction "2_2") (pintype "passive"))
      (node (ref "U0-C") (pin "133") (pinfunction "PB3_133") (pintype "bidirectional"))
    )
    (net (code "79") (name "U1S-CHECK") (class "Default")
      (node (ref "J3-CS") (pin "3") (pinfunction "3_3") (pintype "passive"))
      (node (ref "U0-C") (pin "65") (pinfunction "PE12_65") (pintype "bidirectional"))
    )
    (net (code "80") (name "U2S-CHECK") (class "Default")
      (node (ref "J3-CS") (pin "4") (pinfunction "4_4") (pintype "passive"))
      (node (ref "U0-C") (pin "66") (pinfunction "PE13_66") (pintype "bidirectional"))
    )
    (net (code "81") (name "U2S-ST") (class "Default")
      (node (ref "J3-CS") (pin "7") (pinfunction "7_7") (pintype "passive"))
      (node (ref "U0-C") (pin "69") (pinfunction "PB10_69") (pintype "bidirectional"))
    )
    (net (code "82") (name "U3S-CHECK") (class "Default")
      (node (ref "J3-CS") (pin "5") (pinfunction "5_5") (pintype "passive"))
      (node (ref "U0-C") (pin "67") (pinfunction "PE14_67") (pintype "bidirectional"))
    )
    (net (code "83") (name "U4S-CHECK") (class "Default")
      (node (ref "J3-CS") (pin "6") (pinfunction "6_6") (pintype "passive"))
      (node (ref "U0-C") (pin "68") (pinfunction "PE15_68") (pintype "bidirectional"))
    )
    (net (code "84") (name "US2-STATUS") (class "Default")
      (node (ref "J3-CS") (pin "8") (pinfunction "8_8") (pintype "passive"))
      (node (ref "U0-C") (pin "70") (pinfunction "PB11_70") (pintype "bidirectional"))
    )
    (net (code "85") (name "VDDA") (class "Default")
      (node (ref "FB1-0C") (pin "2") (pinfunction "2_2") (pintype "bidirectional"))
      (node (ref "U0-C") (pin "32") (pinfunction "VREF+_32") (pintype "input"))
      (node (ref "U0-C") (pin "33") (pinfunction "VDDA_33") (pintype "power_in"))
    )
    (net (code "86") (name "VUSB") (class "Default")
      (node (ref "J2-C") (pin "1") (pinfunction "VBUS_1") (pintype "power_in"))
      (node (ref "JP-CP") (pin "4") (pinfunction "4_4") (pintype "passive"))
    )
    (net (code "87") (name "WP") (class "Default")
      (node (ref "U0-C") (pin "78") (pinfunction "PD9_78") (pintype "bidirectional"))
      (node (ref "U1-C") (pin "3") (pinfunction "~{WP}/IO2_3") (pintype "bidirectional"))
    )
    (net (code "88") (name "unconnected-(JP-CS-Pad4)") (class "Default")
      (node (ref "JP-CS") (pin "4") (pinfunction "4_4") (pintype "passive"))
    )
    (net (code "89") (name "unconnected-(S0-0C-P1-Pad4)") (class "Default")
      (node (ref "S0-0C") (pin "4") (pinfunction "P1_4") (pintype "passive"))
    )
    (net (code "90") (name "unconnected-(S0-0C-S1-Pad2)") (class "Default")
      (node (ref "S0-0C") (pin "2") (pinfunction "S1_2") (pintype "passive"))
    )
    (net (code "91") (name "unconnected-(U0-C-PA4-Pad40)") (class "Default")
      (node (ref "U0-C") (pin "40") (pinfunction "PA4_40") (pintype "bidirectional"))
    )
    (net (code "92") (name "unconnected-(U0-C-PA9-Pad101)") (class "Default")
      (node (ref "U0-C") (pin "101") (pinfunction "PA9_101") (pintype "bidirectional"))
    )
    (net (code "93") (name "unconnected-(U0-C-PA15-Pad110)") (class "Default")
      (node (ref "U0-C") (pin "110") (pinfunction "PA15_110") (pintype "bidirectional"))
    )
    (net (code "94") (name "unconnected-(U0-C-PB2-Pad48)") (class "Default")
      (node (ref "U0-C") (pin "48") (pinfunction "PB2_48") (pintype "bidirectional"))
    )
    (net (code "95") (name "unconnected-(U0-C-PB4-Pad134)") (class "Default")
      (node (ref "U0-C") (pin "134") (pinfunction "PB4_134") (pintype "bidirectional"))
    )
    (net (code "96") (name "unconnected-(U0-C-PB5-Pad135)") (class "Default")
      (node (ref "U0-C") (pin "135") (pinfunction "PB5_135") (pintype "bidirectional"))
    )
    (net (code "97") (name "unconnected-(U0-C-PB6-Pad136)") (class "Default")
      (node (ref "U0-C") (pin "136") (pinfunction "PB6_136") (pintype "bidirectional"))
    )
    (net (code "98") (name "unconnected-(U0-C-PB7-Pad137)") (class "Default")
      (node (ref "U0-C") (pin "137") (pinfunction "PB7_137") (pintype "bidirectional"))
    )
    (net (code "99") (name "unconnected-(U0-C-PB8-Pad139)") (class "Default")
      (node (ref "U0-C") (pin "139") (pinfunction "PB8_139") (pintype "bidirectional"))
    )
    (net (code "100") (name "unconnected-(U0-C-PB9-Pad140)") (class "Default")
      (node (ref "U0-C") (pin "140") (pinfunction "PB9_140") (pintype "bidirectional"))
    )
    (net (code "101") (name "unconnected-(U0-C-PB12-Pad73)") (class "Default")
      (node (ref "U0-C") (pin "73") (pinfunction "PB12_73") (pintype "bidirectional"))
    )
    (net (code "102") (name "unconnected-(U0-C-PB13-Pad74)") (class "Default")
      (node (ref "U0-C") (pin "74") (pinfunction "PB13_74") (pintype "bidirectional"))
    )
    (net (code "103") (name "unconnected-(U0-C-PB14-Pad75)") (class "Default")
      (node (ref "U0-C") (pin "75") (pinfunction "PB14_75") (pintype "bidirectional"))
    )
    (net (code "104") (name "unconnected-(U0-C-PB15-Pad76)") (class "Default")
      (node (ref "U0-C") (pin "76") (pinfunction "PB15_76") (pintype "bidirectional"))
    )
    (net (code "105") (name "unconnected-(U0-C-PC0-Pad26)") (class "Default")
      (node (ref "U0-C") (pin "26") (pinfunction "PC0_26") (pintype "bidirectional"))
    )
    (net (code "106") (name "unconnected-(U0-C-PC1-Pad27)") (class "Default")
      (node (ref "U0-C") (pin "27") (pinfunction "PC1_27") (pintype "bidirectional"))
    )
    (net (code "107") (name "unconnected-(U0-C-PC2-Pad28)") (class "Default")
      (node (ref "U0-C") (pin "28") (pinfunction "PC2_28") (pintype "bidirectional"))
    )
    (net (code "108") (name "unconnected-(U0-C-PC3-Pad29)") (class "Default")
      (node (ref "U0-C") (pin "29") (pinfunction "PC3_29") (pintype "bidirectional"))
    )
    (net (code "109") (name "unconnected-(U0-C-PC13-Pad7)") (class "Default")
      (node (ref "U0-C") (pin "7") (pinfunction "PC13_7") (pintype "bidirectional"))
    )
    (net (code "110") (name "unconnected-(U0-C-PC14-Pad8)") (class "Default")
      (node (ref "U0-C") (pin "8") (pinfunction "PC14_8") (pintype "bidirectional"))
    )
    (net (code "111") (name "unconnected-(U0-C-PC15-Pad9)") (class "Default")
      (node (ref "U0-C") (pin "9") (pinfunction "PC15_9") (pintype "bidirectional"))
    )
    (net (code "112") (name "unconnected-(U0-C-PD1-Pad115)") (class "Default")
      (node (ref "U0-C") (pin "115") (pinfunction "PD1_115") (pintype "bidirectional"))
    )
    (net (code "113") (name "unconnected-(U0-C-PD2-Pad116)") (class "Default")
      (node (ref "U0-C") (pin "116") (pinfunction "PD2_116") (pintype "bidirectional"))
    )
    (net (code "114") (name "unconnected-(U0-C-PD3-Pad117)") (class "Default")
      (node (ref "U0-C") (pin "117") (pinfunction "PD3_117") (pintype "bidirectional"))
    )
    (net (code "115") (name "unconnected-(U0-C-PD4-Pad118)") (class "Default")
      (node (ref "U0-C") (pin "118") (pinfunction "PD4_118") (pintype "bidirectional"))
    )
    (net (code "116") (name "unconnected-(U0-C-PD5-Pad119)") (class "Default")
      (node (ref "U0-C") (pin "119") (pinfunction "PD5_119") (pintype "bidirectional"))
    )
    (net (code "117") (name "unconnected-(U0-C-PD6-Pad122)") (class "Default")
      (node (ref "U0-C") (pin "122") (pinfunction "PD6_122") (pintype "bidirectional"))
    )
    (net (code "118") (name "unconnected-(U0-C-PD7-Pad123)") (class "Default")
      (node (ref "U0-C") (pin "123") (pinfunction "PD7_123") (pintype "bidirectional"))
    )
    (net (code "119") (name "unconnected-(U0-C-PD10-Pad79)") (class "Default")
      (node (ref "U0-C") (pin "79") (pinfunction "PD10_79") (pintype "bidirectional"))
    )
    (net (code "120") (name "unconnected-(U0-C-PD11-Pad80)") (class "Default")
      (node (ref "U0-C") (pin "80") (pinfunction "PD11_80") (pintype "bidirectional"))
    )
    (net (code "121") (name "unconnected-(U0-C-PD12-Pad81)") (class "Default")
      (node (ref "U0-C") (pin "81") (pinfunction "PD12_81") (pintype "bidirectional"))
    )
    (net (code "122") (name "unconnected-(U0-C-PD13-Pad82)") (class "Default")
      (node (ref "U0-C") (pin "82") (pinfunction "PD13_82") (pintype "bidirectional"))
    )
    (net (code "123") (name "unconnected-(U0-C-PD14-Pad85)") (class "Default")
      (node (ref "U0-C") (pin "85") (pinfunction "PD14_85") (pintype "bidirectional"))
    )
    (net (code "124") (name "unconnected-(U0-C-PD15-Pad86)") (class "Default")
      (node (ref "U0-C") (pin "86") (pinfunction "PD15_86") (pintype "bidirectional"))
    )
    (net (code "125") (name "unconnected-(U0-C-PE0-Pad141)") (class "Default")
      (node (ref "U0-C") (pin "141") (pinfunction "PE0_141") (pintype "bidirectional"))
    )
    (net (code "126") (name "unconnected-(U0-C-PE1-Pad142)") (class "Default")
      (node (ref "U0-C") (pin "142") (pinfunction "PE1_142") (pintype "bidirectional"))
    )
    (net (code "127") (name "unconnected-(U0-C-PE3-Pad2)") (class "Default")
      (node (ref "U0-C") (pin "2") (pinfunction "PE3_2") (pintype "bidirectional"))
    )
    (net (code "128") (name "unconnected-(U0-C-PE4-Pad3)") (class "Default")
      (node (ref "U0-C") (pin "3") (pinfunction "PE4_3") (pintype "bidirectional"))
    )
    (net (code "129") (name "unconnected-(U0-C-PE5-Pad4)") (class "Default")
      (node (ref "U0-C") (pin "4") (pinfunction "PE5_4") (pintype "bidirectional"))
    )
    (net (code "130") (name "unconnected-(U0-C-PE6-Pad5)") (class "Default")
      (node (ref "U0-C") (pin "5") (pinfunction "PE6_5") (pintype "bidirectional"))
    )
    (net (code "131") (name "unconnected-(U0-C-PE9-Pad60)") (class "Default")
      (node (ref "U0-C") (pin "60") (pinfunction "PE9_60") (pintype "bidirectional"))
    )
    (net (code "132") (name "unconnected-(U0-C-PF0-Pad10)") (class "Default")
      (node (ref "U0-C") (pin "10") (pinfunction "PF0_10") (pintype "bidirectional"))
    )
    (net (code "133") (name "unconnected-(U0-C-PF5-Pad15)") (class "Default")
      (node (ref "U0-C") (pin "15") (pinfunction "PF5_15") (pintype "bidirectional"))
    )
    (net (code "134") (name "unconnected-(U0-C-PF10-Pad22)") (class "Default")
      (node (ref "U0-C") (pin "22") (pinfunction "PF10_22") (pintype "bidirectional"))
    )
    (net (code "135") (name "unconnected-(U0-C-PF11-Pad49)") (class "Default")
      (node (ref "U0-C") (pin "49") (pinfunction "PF11_49") (pintype "bidirectional"))
    )
    (net (code "136") (name "unconnected-(U0-C-PF12-Pad50)") (class "Default")
      (node (ref "U0-C") (pin "50") (pinfunction "PF12_50") (pintype "bidirectional"))
    )
    (net (code "137") (name "unconnected-(U0-C-PG2-Pad87)") (class "Default")
      (node (ref "U0-C") (pin "87") (pinfunction "PG2_87") (pintype "bidirectional"))
    )
    (net (code "138") (name "unconnected-(U0-C-PG3-Pad88)") (class "Default")
      (node (ref "U0-C") (pin "88") (pinfunction "PG3_88") (pintype "bidirectional"))
    )
    (net (code "139") (name "unconnected-(U0-C-PG5-Pad90)") (class "Default")
      (node (ref "U0-C") (pin "90") (pinfunction "PG5_90") (pintype "bidirectional"))
    )
    (net (code "140") (name "unconnected-(U0-C-PG6-Pad91)") (class "Default")
      (node (ref "U0-C") (pin "91") (pinfunction "PG6_91") (pintype "bidirectional"))
    )
    (net (code "141") (name "unconnected-(U0-C-PG7-Pad92)") (class "Default")
      (node (ref "U0-C") (pin "92") (pinfunction "PG7_92") (pintype "bidirectional"))
    )
    (net (code "142") (name "unconnected-(U0-C-PG8-Pad93)") (class "Default")
      (node (ref "U0-C") (pin "93") (pinfunction "PG8_93") (pintype "bidirectional"))
    )
    (net (code "143") (name "unconnected-(U0-C-PG9-Pad124)") (class "Default")
      (node (ref "U0-C") (pin "124") (pinfunction "PG9_124") (pintype "bidirectional"))
    )
    (net (code "144") (name "unconnected-(U0-C-PG10-Pad125)") (class "Default")
      (node (ref "U0-C") (pin "125") (pinfunction "PG10_125") (pintype "bidirectional"))
    )
    (net (code "145") (name "unconnected-(U0-C-PG11-Pad126)") (class "Default")
      (node (ref "U0-C") (pin "126") (pinfunction "PG11_126") (pintype "bidirectional"))
    )
    (net (code "146") (name "unconnected-(U0-C-PG12-Pad127)") (class "Default")
      (node (ref "U0-C") (pin "127") (pinfunction "PG12_127") (pintype "bidirectional"))
    )
    (net (code "147") (name "unconnected-(U0-C-PG13-Pad128)") (class "Default")
      (node (ref "U0-C") (pin "128") (pinfunction "PG13_128") (pintype "bidirectional"))
    )
    (net (code "148") (name "unconnected-(U0-C-PG14-Pad129)") (class "Default")
      (node (ref "U0-C") (pin "129") (pinfunction "PG14_129") (pintype "bidirectional"))
    )
    (net (code "149") (name "unconnected-(U0-C-PG15-Pad132)") (class "Default")
      (node (ref "U0-C") (pin "132") (pinfunction "PG15_132") (pintype "bidirectional"))
    )
    (net (code "150") (name "unconnected-(U1-C-EP-Pad9)") (class "Default")
      (node (ref "U1-C") (pin "9") (pinfunction "EP_9") (pintype "bidirectional"))
    )
  )
)
